# RS-485_422.net
KiCad netlist of a schematic drawn in Altium Designer
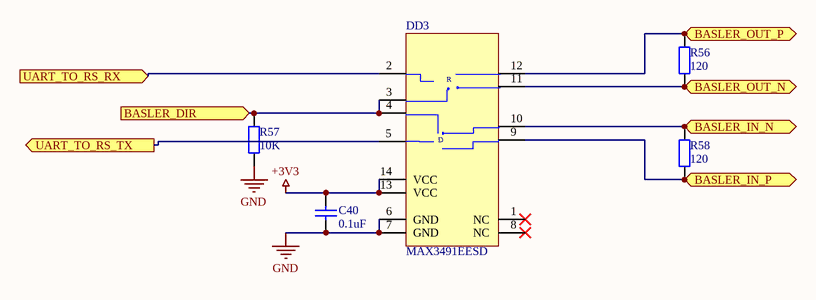
[diagram p0: RS-485_422.SchDoc]

(export (version "E")
  (design (tool "Eeschema 10.0.6"))
  (components
    (comp (ref "C40")
      (value "0.1uF")
      (footprint "C0603")
      (description "Ceramic Capacitor")
      (fields (field (name "VOLTAGE") "50V") (field (name "Comment") "C0603-0.1uF-50V-10%"))
      (libsource (lib "Capacitors_SpekrtAT") (part "C0603-0.1uF-50V-10%"))
    )
    (comp (ref "DD3")
      (value "MAX3491EESD")
      (footprint "SO14")
      (description "Low-Power, Slew-Rate-Limited RS-485/RS-422 Transceiver")
      (libsource (lib "ICs") (part "MAX3491EESD"))
    )
    (comp (ref "R56")
      (value "120")
      (footprint "R0603")
      (description "Chip Resistor")
      (fields (field (name "Comment") "R0603-120-1%"))
      (libsource (lib "Resistors") (part "R0603-120-1%"))
    )
    (comp (ref "R57")
      (value "10K")
      (footprint "R0603")
      (description "Chip Resistor")
      (fields (field (name "Comment") "R0603-10K-1%"))
      (libsource (lib "Resistors") (part "R0603-10K-1%"))
    )
    (comp (ref "R58")
      (value "120")
      (footprint "R0603")
      (description "Chip Resistor")
      (fields (field (name "Comment") "R0603-120-1%"))
      (libsource (lib "Resistors") (part "R0603-120-1%"))
    )
  )
  (nets
    (net (code "1") (name "+3V3") (class "Default")
      (node (ref "C40") (pin "2") (pinfunction "2_2") (pintype "passive"))
      (node (ref "DD3") (pin "13") (pinfunction "VCC_13") (pintype "passive"))
      (node (ref "DD3") (pin "14") (pinfunction "VCC_14") (pintype "passive"))
    )
    (net (code "2") (name "/BASLER_DIR") (class "Default")
      (node (ref "DD3") (pin "3") (pinfunction "~{RE}_3") (pintype "passive"))
      (node (ref "DD3") (pin "4") (pinfunction "DE_4") (pintype "passive"))
      (node (ref "R57") (pin "2") (pinfunction "2_2") (pintype "passive"))
    )
    (net (code "3") (name "/BASLER_IN_N") (class "Default")
      (node (ref "DD3") (pin "10") (pinfunction "Z_10") (pintype "passive"))
      (node (ref "R58") (pin "2") (pinfunction "2_2") (pintype "passive"))
    )
    (net (code "4") (name "/BASLER_IN_P") (class "Default")
      (node (ref "DD3") (pin "9") (pinfunction "Y_9") (pintype "passive"))
      (node (ref "R58") (pin "1") (pinfunction "1_1") (pintype "passive"))
    )
    (net (code "5") (name "/BASLER_OUT_N") (class "Default")
      (node (ref "DD3") (pin "11") (pinfunction "B_11") (pintype "passive"))
      (node (ref "R56") (pin "1") (pinfunction "1_1") (pintype "passive"))
    )
    (net (code "6") (name "/BASLER_OUT_P") (class "Default")
      (node (ref "DD3") (pin "12") (pinfunction "A_12") (pintype "passive"))
      (node (ref "R56") (pin "2") (pinfunction "2_2") (pintype "passive"))
    )
    (net (code "7") (name "/UART_TO_RS_RX") (class "Default")
      (node (ref "DD3") (pin "2") (pinfunction "RO_2") (pintype "passive"))
    )
    (net (code "8") (name "/UART_TO_RS_TX") (class "Default")
      (node (ref "DD3") (pin "5") (pinfunction "DI_5") (pintype "passive"))
    )
    (net (code "9") (name "GND") (class "Default")
      (node (ref "C40") (pin "1") (pinfunction "1_1") (pintype "passive"))
      (node (ref "DD3") (pin "6") (pinfunction "GND_6") (pintype "passive"))
      (node (ref "DD3") (pin "7") (pinfunction "GND_7") (pintype "passive"))
      (node (ref "R57") (pin "1") (pinfunction "1_1") (pintype "passive"))
    )
    (net (code "10") (name "unconnected-(DD3-NC-Pad1)") (class "Default")
      (node (ref "DD3") (pin "1") (pinfunction "NC_1") (pintype "passive+no_connect"))
    )
    (net (code "11") (name "unconnected-(DD3-NC-Pad8)") (class "Default")
      (node (ref "DD3") (pin "8") (pinfunction "NC_8") (pintype "passive+no_connect"))
    )
  )
)
